# minimal_arduino.net
KiCad netlist of a schematic drawn in EAGLE
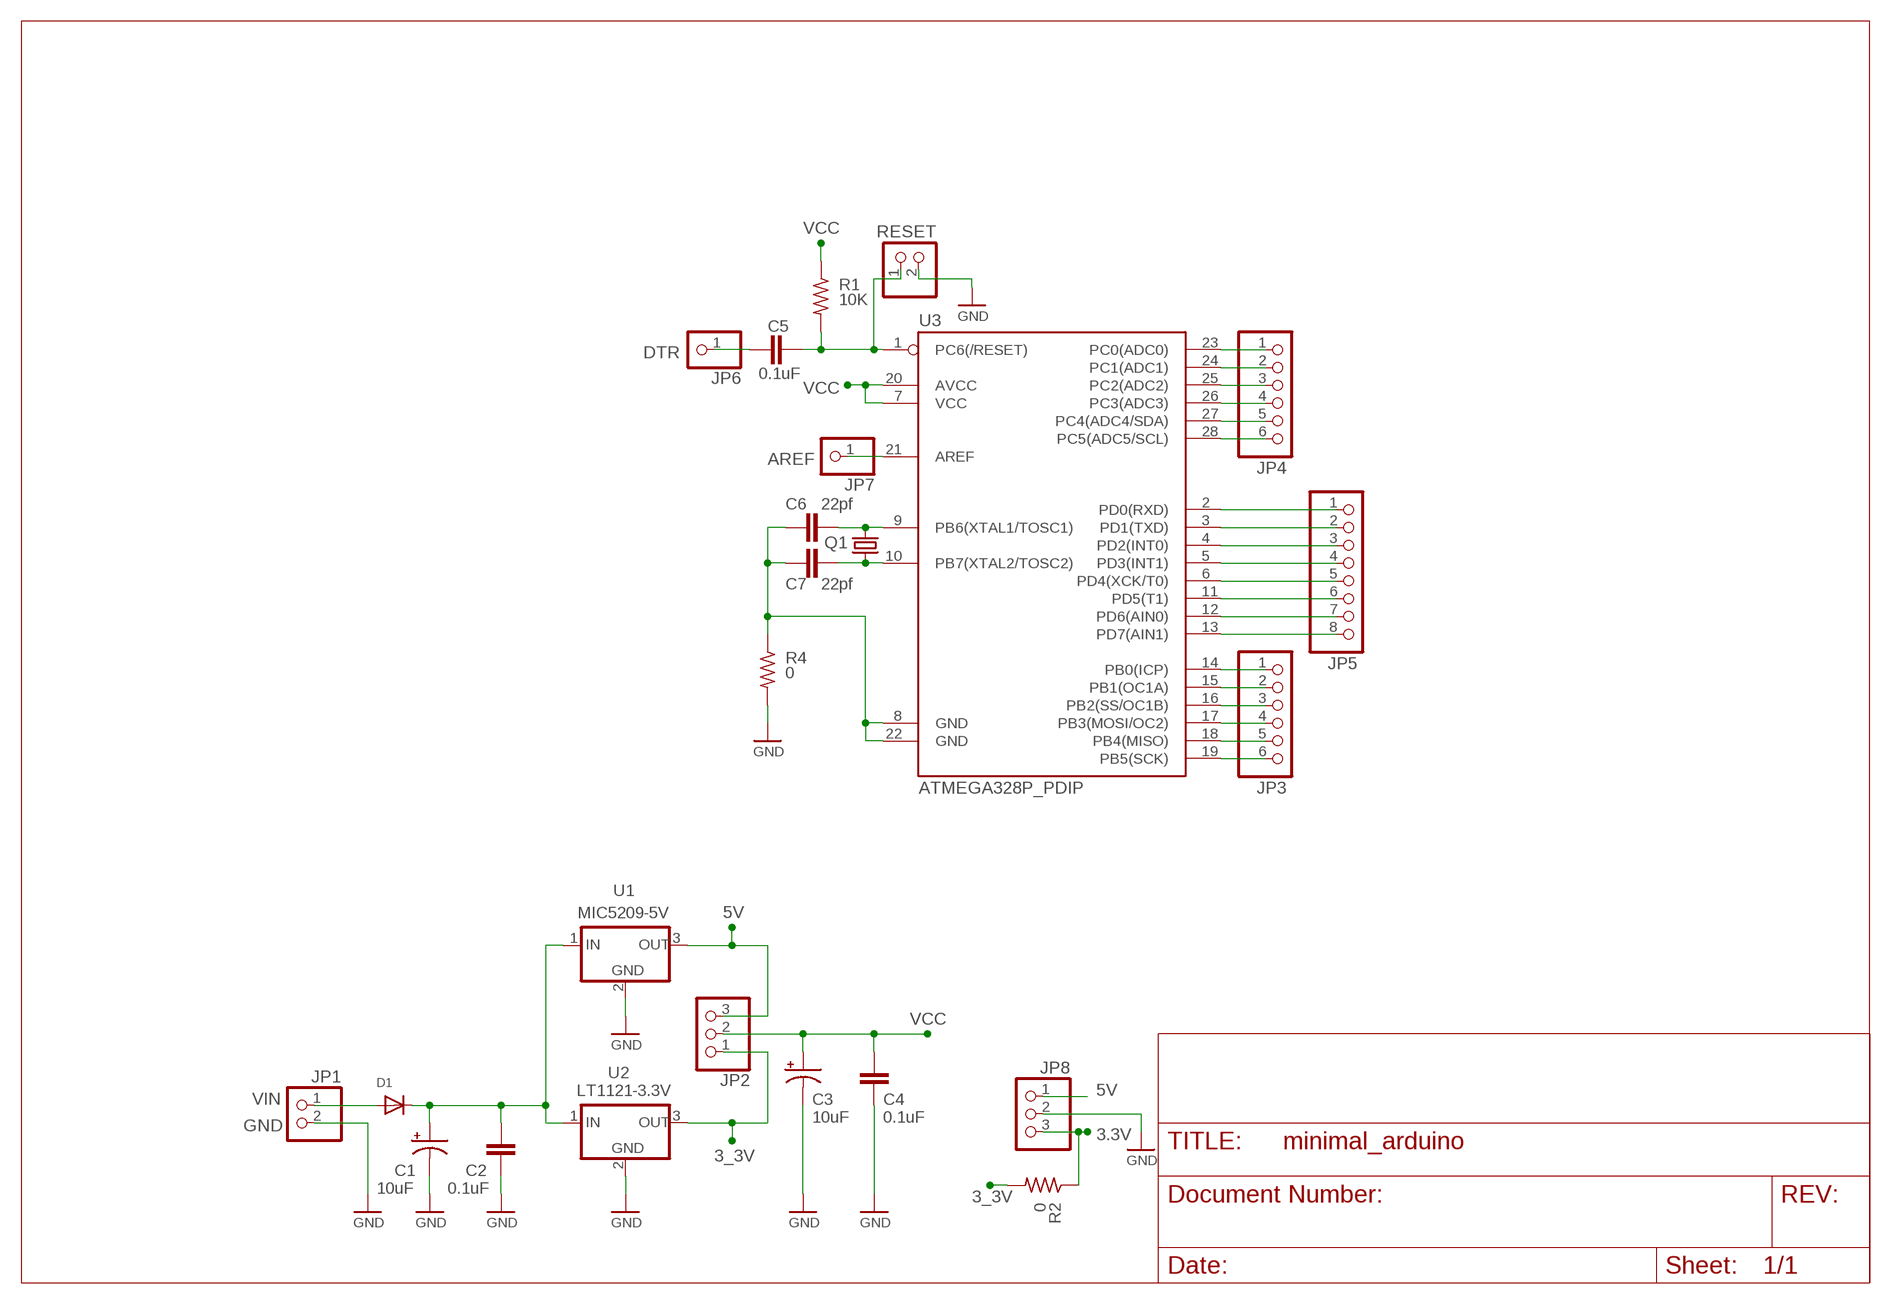
[diagram p0: schematic, sheet 1]

(export (version "E")
  (design (tool "Eeschema 10.0.6"))
  (components
    (comp (ref "C1")
      (value "10uF")
      (footprint "eagle-import:CT3528")
      (libsource (lib "eagle-import") (part "CPOL-USCT3528"))
    )
    (comp (ref "C2")
      (value "0.1uF")
      (footprint "eagle-import:CT3216")
      (libsource (lib "eagle-import") (part "C-EU"))
    )
    (comp (ref "C3")
      (value "10uF")
      (footprint "eagle-import:CT3528")
      (libsource (lib "eagle-import") (part "CPOL-USCT3528"))
    )
    (comp (ref "C4")
      (value "0.1uF")
      (footprint "eagle-import:CT3216")
      (libsource (lib "eagle-import") (part "C-EU"))
    )
    (comp (ref "C5")
      (value "0.1uF")
      (footprint "eagle-import:CT3216")
      (libsource (lib "eagle-import") (part "C-EU"))
    )
    (comp (ref "C6")
      (value "22pf")
      (footprint "eagle-import:CT3216")
      (libsource (lib "eagle-import") (part "C-EU"))
    )
    (comp (ref "C7")
      (value "22pf")
      (footprint "eagle-import:CT3216")
      (libsource (lib "eagle-import") (part "C-EU"))
    )
    (comp (ref "D1")
      (value "DIODESMA")
      (footprint "eagle-import:SMADIODE")
      (libsource (lib "eagle-import") (part "DIODESMA"))
    )
    (comp (ref "JP1")
      (value "PINHD-1X2")
      (footprint "eagle-import:1X02")
      (libsource (lib "eagle-import") (part "PINHD-1X2"))
    )
    (comp (ref "JP2")
      (value "PINHD-1X3")
      (footprint "eagle-import:1X03")
      (libsource (lib "eagle-import") (part "PINHD-1X3"))
    )
    (comp (ref "JP3")
      (value "PINHD-1X6")
      (footprint "eagle-import:1X06")
      (libsource (lib "eagle-import") (part "PINHD-1X6"))
    )
    (comp (ref "JP4")
      (value "PINHD-1X6")
      (footprint "eagle-import:1X06")
      (libsource (lib "eagle-import") (part "PINHD-1X6"))
    )
    (comp (ref "JP5")
      (value "PINHD-1X8")
      (footprint "eagle-import:1X08")
      (libsource (lib "eagle-import") (part "PINHD-1X8"))
    )
    (comp (ref "JP6")
      (value "PINHD-1X1")
      (footprint "eagle-import:1X01")
      (libsource (lib "eagle-import") (part "PINHD-1X1"))
    )
    (comp (ref "JP7")
      (value "PINHD-1X1")
      (footprint "eagle-import:1X01")
      (libsource (lib "eagle-import") (part "PINHD-1X1"))
    )
    (comp (ref "JP8")
      (value "PINHD-1X3")
      (footprint "eagle-import:1X03")
      (libsource (lib "eagle-import") (part "PINHD-1X3"))
    )
    (comp (ref "Q1")
      (value "CRYSTALHC18U-V")
      (footprint "eagle-import:HC18U-V")
      (libsource (lib "eagle-import") (part "CRYSTALHC18U-V"))
    )
    (comp (ref "R1")
      (value "10K")
      (footprint "eagle-import:M1406")
      (libsource (lib "eagle-import") (part "R-US_M1406"))
    )
    (comp (ref "R2")
      (value "0")
      (footprint "eagle-import:M1406")
      (libsource (lib "eagle-import") (part "R-US_M1406"))
    )
    (comp (ref "R4")
      (value "0")
      (footprint "eagle-import:M1406")
      (libsource (lib "eagle-import") (part "R-US_M1406"))
    )
    (comp (ref "RESET")
      (value "PINHD-1X2")
      (footprint "eagle-import:1X02")
      (libsource (lib "eagle-import") (part "PINHD-1X2"))
    )
    (comp (ref "U1")
      (value "MIC5209-5V")
      (footprint "eagle-import:SOT223_LT")
      (libsource (lib "eagle-import") (part "MIC5209"))
    )
    (comp (ref "U2")
      (value "LT1121-3.3V")
      (footprint "eagle-import:SOT223_LT")
      (libsource (lib "eagle-import") (part "LT1121-3.3VSOT223-LT"))
    )
    (comp (ref "U3")
      (value "ATMEGA328P_PDIP")
      (footprint "eagle-import:DIL28-3")
      (libsource (lib "eagle-import") (part "ATMEGA328P_PDIP"))
    )
  )
  (nets
    (net (code "1") (name "/3.3V") (class "Default")
      (node (ref "JP8") (pin "3") (pinfunction "3_3") (pintype "passive"))
      (node (ref "R2") (pin "1") (pinfunction "1_1") (pintype "passive"))
    )
    (net (code "2") (name "/3_3V") (class "Default")
      (node (ref "JP2") (pin "1") (pinfunction "1_1") (pintype "passive"))
      (node (ref "R2") (pin "2") (pinfunction "2_2") (pintype "passive"))
      (node (ref "U2") (pin "3") (pinfunction "VO_3") (pintype "passive"))
    )
    (net (code "3") (name "/5V") (class "Default")
      (node (ref "JP2") (pin "3") (pinfunction "3_3") (pintype "passive"))
      (node (ref "JP8") (pin "1") (pinfunction "1_1") (pintype "passive"))
      (node (ref "U1") (pin "3") (pinfunction "VO_3") (pintype "passive"))
    )
    (net (code "4") (name "/AREF") (class "Default")
      (node (ref "JP7") (pin "1") (pinfunction "1_1") (pintype "passive"))
      (node (ref "U3") (pin "21") (pinfunction "AREF_21") (pintype "bidirectional"))
    )
    (net (code "5") (name "/DTR") (class "Default")
      (node (ref "C5") (pin "+") (pinfunction "1_+") (pintype "passive"))
      (node (ref "JP6") (pin "1") (pinfunction "1_1") (pintype "passive"))
    )
    (net (code "6") (name "/VCC") (class "Default")
      (node (ref "C3") (pin "+") (pinfunction "+_+") (pintype "passive"))
      (node (ref "C4") (pin "+") (pinfunction "1_+") (pintype "passive"))
      (node (ref "JP2") (pin "2") (pinfunction "2_2") (pintype "passive"))
      (node (ref "R1") (pin "1") (pinfunction "1_1") (pintype "passive"))
      (node (ref "U3") (pin "20") (pinfunction "AVCC_20") (pintype "bidirectional"))
      (node (ref "U3") (pin "7") (pinfunction "VCC_7") (pintype "bidirectional"))
    )
    (net (code "7") (name "/VIN") (class "Default")
      (node (ref "D1") (pin "A") (pinfunction "A_A") (pintype "passive"))
      (node (ref "JP1") (pin "1") (pinfunction "1_1") (pintype "passive"))
    )
    (net (code "8") (name "GND") (class "Default")
      (node (ref "C1") (pin "-") (pinfunction "-_-") (pintype "passive"))
      (node (ref "C2") (pin "-") (pinfunction "2_-") (pintype "passive"))
      (node (ref "C3") (pin "-") (pinfunction "-_-") (pintype "passive"))
      (node (ref "C4") (pin "-") (pinfunction "2_-") (pintype "passive"))
      (node (ref "JP1") (pin "2") (pinfunction "2_2") (pintype "passive"))
      (node (ref "JP8") (pin "2") (pinfunction "2_2") (pintype "passive"))
      (node (ref "R4") (pin "2") (pinfunction "2_2") (pintype "passive"))
      (node (ref "RESET") (pin "2") (pinfunction "2_2") (pintype "passive"))
      (node (ref "U1") (pin "2") (pinfunction "GND_2") (pintype "input"))
      (node (ref "U2") (pin "2") (pinfunction "GND_2") (pintype "input"))
    )
    (net (code "9") (name "Net-(C2-1)") (class "Default")
      (node (ref "C1") (pin "+") (pinfunction "+_+") (pintype "passive"))
      (node (ref "C2") (pin "+") (pinfunction "1_+") (pintype "passive"))
      (node (ref "D1") (pin "C") (pinfunction "C_C") (pintype "passive"))
      (node (ref "U1") (pin "1") (pinfunction "VI_1") (pintype "input"))
      (node (ref "U2") (pin "1") (pinfunction "VI_1") (pintype "input"))
    )
    (net (code "10") (name "Net-(C5-2)") (class "Default")
      (node (ref "C5") (pin "-") (pinfunction "2_-") (pintype "passive"))
      (node (ref "R1") (pin "2") (pinfunction "2_2") (pintype "passive"))
      (node (ref "RESET") (pin "1") (pinfunction "1_1") (pintype "passive"))
      (node (ref "U3") (pin "1") (pinfunction "PC6(/RESET)_1") (pintype "bidirectional"))
    )
    (net (code "11") (name "Net-(C6-1)") (class "Default")
      (node (ref "C6") (pin "+") (pinfunction "1_+") (pintype "passive"))
      (node (ref "C7") (pin "+") (pinfunction "1_+") (pintype "passive"))
      (node (ref "R4") (pin "1") (pinfunction "1_1") (pintype "passive"))
      (node (ref "U3") (pin "22") (pinfunction "GND_22") (pintype "bidirectional"))
      (node (ref "U3") (pin "8") (pinfunction "GND_8") (pintype "bidirectional"))
    )
    (net (code "12") (name "Net-(C6-2)") (class "Default")
      (node (ref "C6") (pin "-") (pinfunction "2_-") (pintype "passive"))
      (node (ref "Q1") (pin "2") (pinfunction "2_2") (pintype "passive"))
      (node (ref "U3") (pin "9") (pinfunction "PB6(XTAL1/TOSC1)_9") (pintype "bidirectional"))
    )
    (net (code "13") (name "Net-(C7-2)") (class "Default")
      (node (ref "C7") (pin "-") (pinfunction "2_-") (pintype "passive"))
      (node (ref "Q1") (pin "1") (pinfunction "1_1") (pintype "passive"))
      (node (ref "U3") (pin "10") (pinfunction "PB7(XTAL2/TOSC2)_10") (pintype "bidirectional"))
    )
    (net (code "14") (name "Net-(U3-PB0(ICP))") (class "Default")
      (node (ref "JP3") (pin "1") (pinfunction "1_1") (pintype "passive"))
      (node (ref "U3") (pin "14") (pinfunction "PB0(ICP)_14") (pintype "bidirectional"))
    )
    (net (code "15") (name "Net-(U3-PB1(OC1A))") (class "Default")
      (node (ref "JP3") (pin "2") (pinfunction "2_2") (pintype "passive"))
      (node (ref "U3") (pin "15") (pinfunction "PB1(OC1A)_15") (pintype "bidirectional"))
    )
    (net (code "16") (name "Net-(U3-PB2(SS{slash}OC1B))") (class "Default")
      (node (ref "JP3") (pin "3") (pinfunction "3_3") (pintype "passive"))
      (node (ref "U3") (pin "16") (pinfunction "PB2(SS/OC1B)_16") (pintype "bidirectional"))
    )
    (net (code "17") (name "Net-(U3-PB3(MOSI{slash}OC2))") (class "Default")
      (node (ref "JP3") (pin "4") (pinfunction "4_4") (pintype "passive"))
      (node (ref "U3") (pin "17") (pinfunction "PB3(MOSI/OC2)_17") (pintype "bidirectional"))
    )
    (net (code "18") (name "Net-(U3-PB4(MISO))") (class "Default")
      (node (ref "JP3") (pin "5") (pinfunction "5_5") (pintype "passive"))
      (node (ref "U3") (pin "18") (pinfunction "PB4(MISO)_18") (pintype "bidirectional"))
    )
    (net (code "19") (name "Net-(U3-PB5(SCK))") (class "Default")
      (node (ref "JP3") (pin "6") (pinfunction "6_6") (pintype "passive"))
      (node (ref "U3") (pin "19") (pinfunction "PB5(SCK)_19") (pintype "bidirectional"))
    )
    (net (code "20") (name "Net-(U3-PC0(ADC0))") (class "Default")
      (node (ref "JP4") (pin "1") (pinfunction "1_1") (pintype "passive"))
      (node (ref "U3") (pin "23") (pinfunction "PC0(ADC0)_23") (pintype "bidirectional"))
    )
    (net (code "21") (name "Net-(U3-PC1(ADC1))") (class "Default")
      (node (ref "JP4") (pin "2") (pinfunction "2_2") (pintype "passive"))
      (node (ref "U3") (pin "24") (pinfunction "PC1(ADC1)_24") (pintype "bidirectional"))
    )
    (net (code "22") (name "Net-(U3-PC2(ADC2))") (class "Default")
      (node (ref "JP4") (pin "3") (pinfunction "3_3") (pintype "passive"))
      (node (ref "U3") (pin "25") (pinfunction "PC2(ADC2)_25") (pintype "bidirectional"))
    )
    (net (code "23") (name "Net-(U3-PC3(ADC3))") (class "Default")
      (node (ref "JP4") (pin "4") (pinfunction "4_4") (pintype "passive"))
      (node (ref "U3") (pin "26") (pinfunction "PC3(ADC3)_26") (pintype "bidirectional"))
    )
    (net (code "24") (name "Net-(U3-PC4(ADC4{slash}SDA))") (class "Default")
      (node (ref "JP4") (pin "5") (pinfunction "5_5") (pintype "passive"))
      (node (ref "U3") (pin "27") (pinfunction "PC4(ADC4/SDA)_27") (pintype "bidirectional"))
    )
    (net (code "25") (name "Net-(U3-PC5(ADC5{slash}SCL))") (class "Default")
      (node (ref "JP4") (pin "6") (pinfunction "6_6") (pintype "passive"))
      (node (ref "U3") (pin "28") (pinfunction "PC5(ADC5/SCL)_28") (pintype "bidirectional"))
    )
    (net (code "26") (name "Net-(U3-PD0(RXD))") (class "Default")
      (node (ref "JP5") (pin "1") (pinfunction "1_1") (pintype "passive"))
      (node (ref "U3") (pin "2") (pinfunction "PD0(RXD)_2") (pintype "bidirectional"))
    )
    (net (code "27") (name "Net-(U3-PD1(TXD))") (class "Default")
      (node (ref "JP5") (pin "2") (pinfunction "2_2") (pintype "passive"))
      (node (ref "U3") (pin "3") (pinfunction "PD1(TXD)_3") (pintype "bidirectional"))
    )
    (net (code "28") (name "Net-(U3-PD2(INT0))") (class "Default")
      (node (ref "JP5") (pin "3") (pinfunction "3_3") (pintype "passive"))
      (node (ref "U3") (pin "4") (pinfunction "PD2(INT0)_4") (pintype "bidirectional"))
    )
    (net (code "29") (name "Net-(U3-PD3(INT1))") (class "Default")
      (node (ref "JP5") (pin "4") (pinfunction "4_4") (pintype "passive"))
      (node (ref "U3") (pin "5") (pinfunction "PD3(INT1)_5") (pintype "bidirectional"))
    )
    (net (code "30") (name "Net-(U3-PD4(XCK{slash}T0))") (class "Default")
      (node (ref "JP5") (pin "5") (pinfunction "5_5") (pintype "passive"))
      (node (ref "U3") (pin "6") (pinfunction "PD4(XCK/T0)_6") (pintype "bidirectional"))
    )
    (net (code "31") (name "Net-(U3-PD5(T1))") (class "Default")
      (node (ref "JP5") (pin "6") (pinfunction "6_6") (pintype "passive"))
      (node (ref "U3") (pin "11") (pinfunction "PD5(T1)_11") (pintype "bidirectional"))
    )
    (net (code "32") (name "Net-(U3-PD6(AIN0))") (class "Default")
      (node (ref "JP5") (pin "7") (pinfunction "7_7") (pintype "passive"))
      (node (ref "U3") (pin "12") (pinfunction "PD6(AIN0)_12") (pintype "bidirectional"))
    )
    (net (code "33") (name "Net-(U3-PD7(AIN1))") (class "Default")
      (node (ref "JP5") (pin "8") (pinfunction "8_8") (pintype "passive"))
      (node (ref "U3") (pin "13") (pinfunction "PD7(AIN1)_13") (pintype "bidirectional"))
    )
  )
)
